# fCPU.net
KiCad netlist of a schematic drawn in EAGLE
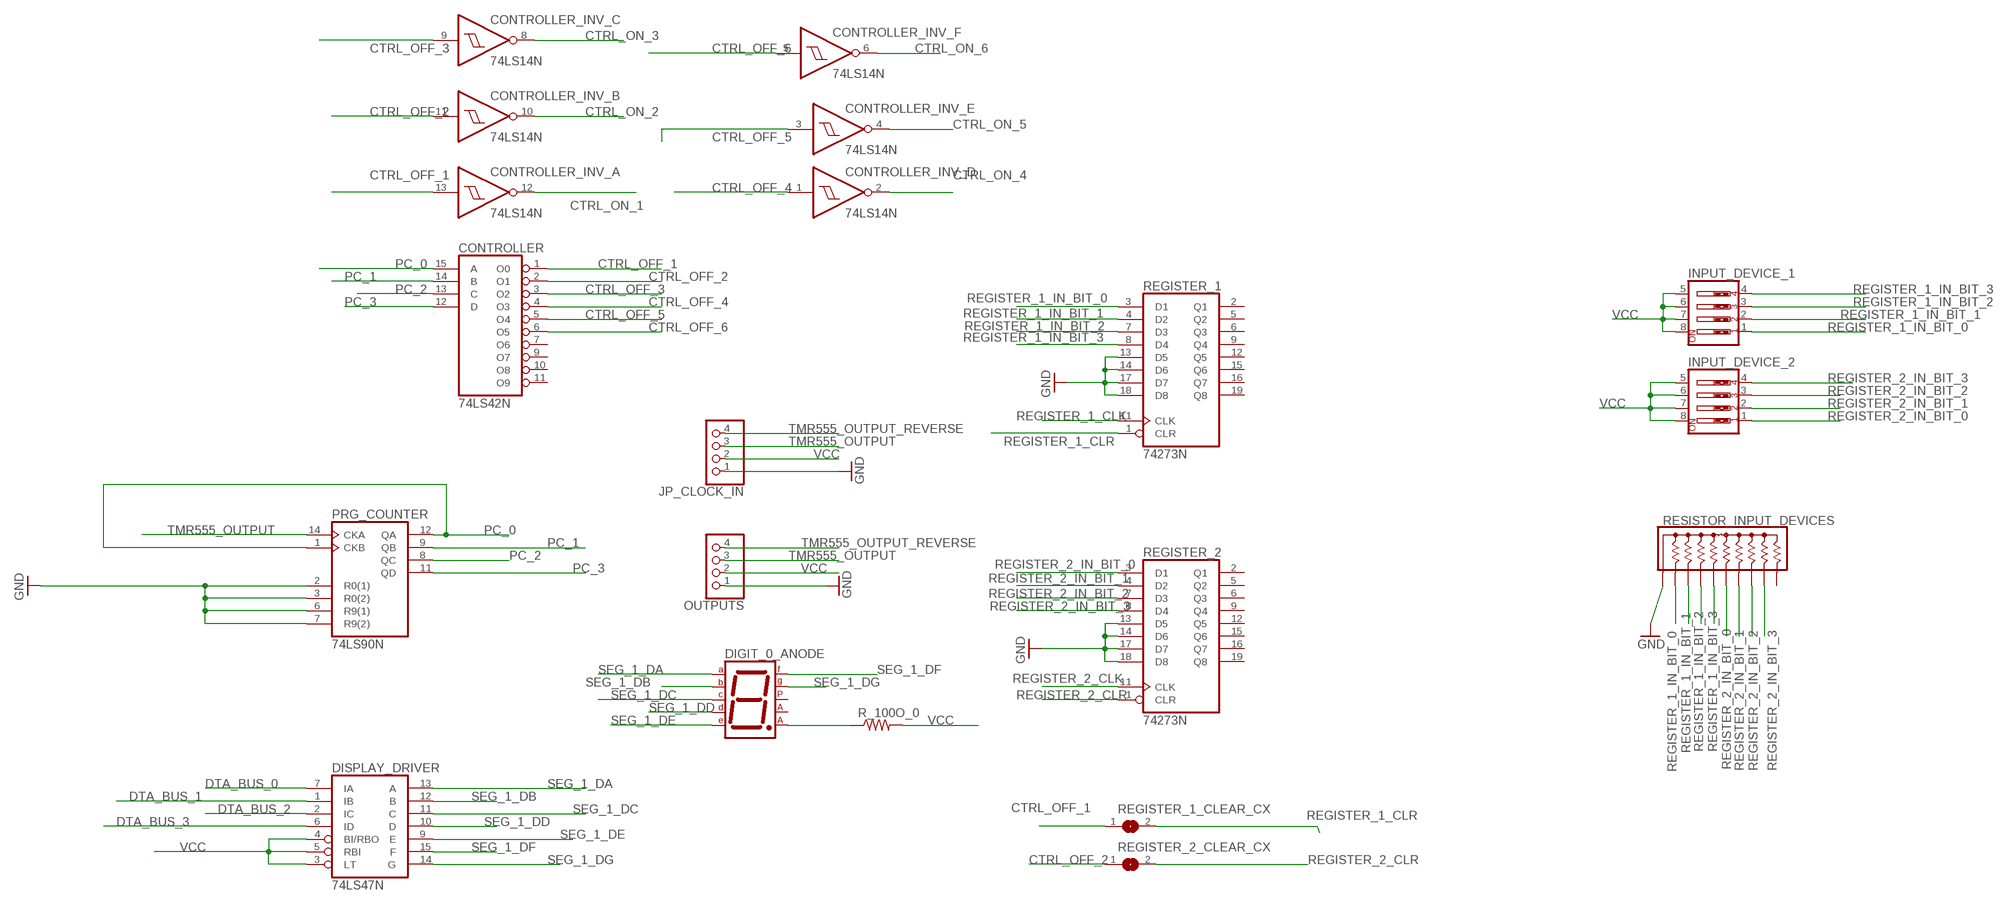
[diagram p0: schematic, sheet 1]

(export (version "E")
  (design (tool "Eeschema 10.0.6"))
  (components
    (comp (ref "CONTROLLER")
      (value "74LS42N")
      (footprint "eagle-import:DIL16")
      (libsource (lib "eagle-import") (part "7442NLS"))
    )
    (comp (ref "CONTROLLER_INV_")
      (value "74LS14N")
      (footprint "eagle-import:DIL14")
      (libsource (lib "eagle-import") (part "7414NLS"))
    )
    (comp (ref "DIGIT_0_ANODE")
      (value "7SEG-CA")
      (footprint "eagle-import:7SEG-13")
      (libsource (lib "eagle-import") (part "7SEG-CA"))
    )
    (comp (ref "DISPLAY_DRIVER")
      (value "74LS47N")
      (footprint "eagle-import:DIL16")
      (libsource (lib "eagle-import") (part "7447NLS"))
    )
    (comp (ref "INPUT_DEVICE_1")
      (value "SW_DIP-4")
      (footprint "eagle-import:EDG-04")
      (libsource (lib "eagle-import") (part "SW_DIP-4"))
    )
    (comp (ref "INPUT_DEVICE_2")
      (value "SW_DIP-4")
      (footprint "eagle-import:EDG-04")
      (libsource (lib "eagle-import") (part "SW_DIP-4"))
    )
    (comp (ref "JP_CLOCK_IN")
      (value "PINHD-1X4")
      (footprint "eagle-import:1X04")
      (libsource (lib "eagle-import") (part "PINHD-1X4"))
    )
    (comp (ref "OUTPUTS")
      (value "PINHD-1X4")
      (footprint "eagle-import:1X04")
      (libsource (lib "eagle-import") (part "PINHD-1X4"))
    )
    (comp (ref "PRG_COUNTER")
      (value "74LS90N")
      (footprint "eagle-import:DIL14")
      (libsource (lib "eagle-import") (part "7490NLS"))
    )
    (comp (ref "REGISTER_1")
      (value "74273N")
      (footprint "eagle-import:DIL20")
      (libsource (lib "eagle-import") (part "74273N"))
    )
    (comp (ref "REGISTER_1_CLEAR_CX")
      (value "SOLDERJUMPERREFLOW")
      (footprint "eagle-import:SOLDERJUMPER_REFLOW")
      (libsource (lib "eagle-import") (part "SOLDERJUMPERREFLOW"))
    )
    (comp (ref "REGISTER_2")
      (value "74273N")
      (footprint "eagle-import:DIL20")
      (libsource (lib "eagle-import") (part "74273N"))
    )
    (comp (ref "REGISTER_2_CLEAR_CX")
      (value "SOLDERJUMPERREFLOW")
      (footprint "eagle-import:SOLDERJUMPER_REFLOW")
      (libsource (lib "eagle-import") (part "SOLDERJUMPERREFLOW"))
    )
    (comp (ref "RESISTOR_INPUT_DEVICES")
      (value "4610X")
      (footprint "eagle-import:SIP10")
      (libsource (lib "eagle-import") (part "4610X"))
    )
    (comp (ref "R_100O_0")
      (value "R-US_R1206")
      (footprint "eagle-import:R1206")
      (libsource (lib "eagle-import") (part "R-US_R1206"))
    )
  )
  (nets
    (net (code "1") (name "/CTRL_OFF_1") (class "Default")
      (node (ref "CONTROLLER") (pin "1") (pinfunction "O0_1") (pintype "output"))
      (node (ref "CONTROLLER_INV_") (pin "13") (pinfunction "I_13") (pintype "input"))
      (node (ref "REGISTER_1_CLEAR_CX") (pin "1") (pinfunction "1_1") (pintype "passive"))
    )
    (net (code "2") (name "/CTRL_OFF_2") (class "Default")
      (node (ref "CONTROLLER") (pin "2") (pinfunction "O1_2") (pintype "output"))
      (node (ref "CONTROLLER_INV_") (pin "11") (pinfunction "I_11") (pintype "input"))
      (node (ref "REGISTER_2_CLEAR_CX") (pin "1") (pinfunction "1_1") (pintype "passive"))
    )
    (net (code "3") (name "/CTRL_OFF_3") (class "Default")
      (node (ref "CONTROLLER") (pin "3") (pinfunction "O2_3") (pintype "output"))
      (node (ref "CONTROLLER_INV_") (pin "9") (pinfunction "I_9") (pintype "input"))
    )
    (net (code "4") (name "/CTRL_OFF_4") (class "Default")
      (node (ref "CONTROLLER") (pin "4") (pinfunction "O3_4") (pintype "output"))
      (node (ref "CONTROLLER_INV_") (pin "1") (pinfunction "I_1") (pintype "input"))
    )
    (net (code "5") (name "/CTRL_OFF_5") (class "Default")
      (node (ref "CONTROLLER") (pin "5") (pinfunction "O4_5") (pintype "output"))
      (node (ref "CONTROLLER_INV_") (pin "3") (pinfunction "I_3") (pintype "input"))
    )
    (net (code "6") (name "/CTRL_OFF_6") (class "Default")
      (node (ref "CONTROLLER") (pin "6") (pinfunction "O5_6") (pintype "output"))
      (node (ref "CONTROLLER_INV_") (pin "5") (pinfunction "I_5") (pintype "input"))
    )
    (net (code "7") (name "/CTRL_ON_1") (class "Default")
      (node (ref "CONTROLLER_INV_") (pin "12") (pinfunction "O_12") (pintype "output"))
    )
    (net (code "8") (name "/CTRL_ON_2") (class "Default")
      (node (ref "CONTROLLER_INV_") (pin "10") (pinfunction "O_10") (pintype "output"))
    )
    (net (code "9") (name "/CTRL_ON_3") (class "Default")
      (node (ref "CONTROLLER_INV_") (pin "8") (pinfunction "O_8") (pintype "output"))
    )
    (net (code "10") (name "/CTRL_ON_4") (class "Default")
      (node (ref "CONTROLLER_INV_") (pin "2") (pinfunction "O_2") (pintype "output"))
    )
    (net (code "11") (name "/CTRL_ON_5") (class "Default")
      (node (ref "CONTROLLER_INV_") (pin "4") (pinfunction "O_4") (pintype "output"))
    )
    (net (code "12") (name "/CTRL_ON_6") (class "Default")
      (node (ref "CONTROLLER_INV_") (pin "6") (pinfunction "O_6") (pintype "output"))
    )
    (net (code "13") (name "/DTA_BUS_0") (class "Default")
      (node (ref "DISPLAY_DRIVER") (pin "7") (pinfunction "IA_7") (pintype "input"))
    )
    (net (code "14") (name "/DTA_BUS_1") (class "Default")
      (node (ref "DISPLAY_DRIVER") (pin "1") (pinfunction "IB_1") (pintype "input"))
    )
    (net (code "15") (name "/DTA_BUS_2") (class "Default")
      (node (ref "DISPLAY_DRIVER") (pin "2") (pinfunction "IC_2") (pintype "input"))
    )
    (net (code "16") (name "/DTA_BUS_3") (class "Default")
      (node (ref "DISPLAY_DRIVER") (pin "6") (pinfunction "ID_6") (pintype "input"))
    )
    (net (code "17") (name "/PC_0") (class "Default")
      (node (ref "CONTROLLER") (pin "15") (pinfunction "A_15") (pintype "input"))
      (node (ref "PRG_COUNTER") (pin "1") (pinfunction "CKB_1") (pintype "input"))
      (node (ref "PRG_COUNTER") (pin "12") (pinfunction "QA_12") (pintype "output"))
    )
    (net (code "18") (name "/PC_1") (class "Default")
      (node (ref "CONTROLLER") (pin "14") (pinfunction "B_14") (pintype "input"))
      (node (ref "PRG_COUNTER") (pin "9") (pinfunction "QB_9") (pintype "output"))
    )
    (net (code "19") (name "/PC_2") (class "Default")
      (node (ref "CONTROLLER") (pin "13") (pinfunction "C_13") (pintype "input"))
      (node (ref "PRG_COUNTER") (pin "8") (pinfunction "QC_8") (pintype "output"))
    )
    (net (code "20") (name "/PC_3") (class "Default")
      (node (ref "CONTROLLER") (pin "12") (pinfunction "D_12") (pintype "input"))
      (node (ref "PRG_COUNTER") (pin "11") (pinfunction "QD_11") (pintype "output"))
    )
    (net (code "21") (name "/REGISTER_1_CLK") (class "Default")
      (node (ref "REGISTER_1") (pin "11") (pinfunction "CLK_11") (pintype "input"))
    )
    (net (code "22") (name "/REGISTER_1_CLR") (class "Default")
      (node (ref "REGISTER_1") (pin "1") (pinfunction "CLR_1") (pintype "input"))
      (node (ref "REGISTER_1_CLEAR_CX") (pin "2") (pinfunction "2_2") (pintype "passive"))
    )
    (net (code "23") (name "/REGISTER_1_IN_BIT_0") (class "Default")
      (node (ref "INPUT_DEVICE_1") (pin "1") (pinfunction "1_1") (pintype "passive"))
      (node (ref "REGISTER_1") (pin "3") (pinfunction "D1_3") (pintype "input"))
      (node (ref "RESISTOR_INPUT_DEVICES") (pin "2") (pinfunction "2_2") (pintype "passive"))
    )
    (net (code "24") (name "/REGISTER_1_IN_BIT_1") (class "Default")
      (node (ref "INPUT_DEVICE_1") (pin "2") (pinfunction "2_2") (pintype "passive"))
      (node (ref "REGISTER_1") (pin "4") (pinfunction "D2_4") (pintype "input"))
      (node (ref "RESISTOR_INPUT_DEVICES") (pin "3") (pinfunction "3_3") (pintype "passive"))
    )
    (net (code "25") (name "/REGISTER_1_IN_BIT_2") (class "Default")
      (node (ref "INPUT_DEVICE_1") (pin "3") (pinfunction "3_3") (pintype "passive"))
      (node (ref "REGISTER_1") (pin "7") (pinfunction "D3_7") (pintype "input"))
      (node (ref "RESISTOR_INPUT_DEVICES") (pin "4") (pinfunction "4_4") (pintype "passive"))
    )
    (net (code "26") (name "/REGISTER_1_IN_BIT_3") (class "Default")
      (node (ref "INPUT_DEVICE_1") (pin "4") (pinfunction "4_4") (pintype "passive"))
      (node (ref "REGISTER_1") (pin "8") (pinfunction "D4_8") (pintype "input"))
      (node (ref "RESISTOR_INPUT_DEVICES") (pin "5") (pinfunction "5_5") (pintype "passive"))
    )
    (net (code "27") (name "/REGISTER_2_CLK") (class "Default")
      (node (ref "REGISTER_2") (pin "11") (pinfunction "CLK_11") (pintype "input"))
    )
    (net (code "28") (name "/REGISTER_2_CLR") (class "Default")
      (node (ref "REGISTER_2") (pin "1") (pinfunction "CLR_1") (pintype "input"))
      (node (ref "REGISTER_2_CLEAR_CX") (pin "2") (pinfunction "2_2") (pintype "passive"))
    )
    (net (code "29") (name "/REGISTER_2_IN_BIT_0") (class "Default")
      (node (ref "INPUT_DEVICE_2") (pin "1") (pinfunction "1_1") (pintype "passive"))
      (node (ref "REGISTER_2") (pin "3") (pinfunction "D1_3") (pintype "input"))
      (node (ref "RESISTOR_INPUT_DEVICES") (pin "6") (pinfunction "6_6") (pintype "passive"))
    )
    (net (code "30") (name "/REGISTER_2_IN_BIT_1") (class "Default")
      (node (ref "INPUT_DEVICE_2") (pin "2") (pinfunction "2_2") (pintype "passive"))
      (node (ref "REGISTER_2") (pin "4") (pinfunction "D2_4") (pintype "input"))
      (node (ref "RESISTOR_INPUT_DEVICES") (pin "7") (pinfunction "7_7") (pintype "passive"))
    )
    (net (code "31") (name "/REGISTER_2_IN_BIT_2") (class "Default")
      (node (ref "INPUT_DEVICE_2") (pin "3") (pinfunction "3_3") (pintype "passive"))
      (node (ref "REGISTER_2") (pin "7") (pinfunction "D3_7") (pintype "input"))
      (node (ref "RESISTOR_INPUT_DEVICES") (pin "8") (pinfunction "8_8") (pintype "passive"))
    )
    (net (code "32") (name "/REGISTER_2_IN_BIT_3") (class "Default")
      (node (ref "INPUT_DEVICE_2") (pin "4") (pinfunction "4_4") (pintype "passive"))
      (node (ref "REGISTER_2") (pin "8") (pinfunction "D4_8") (pintype "input"))
      (node (ref "RESISTOR_INPUT_DEVICES") (pin "9") (pinfunction "9_9") (pintype "passive"))
    )
    (net (code "33") (name "/SEG_1_DA") (class "Default")
      (node (ref "DIGIT_0_ANODE") (pin "7") (pinfunction "A_7") (pintype "passive"))
      (node (ref "DISPLAY_DRIVER") (pin "13") (pinfunction "A_13") (pintype "output"))
    )
    (net (code "34") (name "/SEG_1_DB") (class "Default")
      (node (ref "DIGIT_0_ANODE") (pin "6") (pinfunction "B_6") (pintype "passive"))
      (node (ref "DISPLAY_DRIVER") (pin "12") (pinfunction "B_12") (pintype "output"))
    )
    (net (code "35") (name "/SEG_1_DC") (class "Default")
      (node (ref "DIGIT_0_ANODE") (pin "4") (pinfunction "C_4") (pintype "passive"))
      (node (ref "DISPLAY_DRIVER") (pin "11") (pinfunction "C_11") (pintype "output"))
    )
    (net (code "36") (name "/SEG_1_DD") (class "Default")
      (node (ref "DIGIT_0_ANODE") (pin "2") (pinfunction "D_2") (pintype "passive"))
      (node (ref "DISPLAY_DRIVER") (pin "10") (pinfunction "D_10") (pintype "output"))
    )
    (net (code "37") (name "/SEG_1_DE") (class "Default")
      (node (ref "DIGIT_0_ANODE") (pin "1") (pinfunction "E_1") (pintype "passive"))
      (node (ref "DISPLAY_DRIVER") (pin "9") (pinfunction "E_9") (pintype "output"))
    )
    (net (code "38") (name "/SEG_1_DF") (class "Default")
      (node (ref "DIGIT_0_ANODE") (pin "9") (pinfunction "F_9") (pintype "passive"))
      (node (ref "DISPLAY_DRIVER") (pin "15") (pinfunction "F_15") (pintype "output"))
    )
    (net (code "39") (name "/SEG_1_DG") (class "Default")
      (node (ref "DIGIT_0_ANODE") (pin "10") (pinfunction "G_10") (pintype "passive"))
      (node (ref "DISPLAY_DRIVER") (pin "14") (pinfunction "G_14") (pintype "output"))
    )
    (net (code "40") (name "/TMR555_OUTPUT") (class "Default")
      (node (ref "JP_CLOCK_IN") (pin "3") (pinfunction "3_3") (pintype "passive"))
      (node (ref "OUTPUTS") (pin "3") (pinfunction "3_3") (pintype "passive"))
      (node (ref "PRG_COUNTER") (pin "14") (pinfunction "CKA_14") (pintype "input"))
    )
    (net (code "41") (name "/TMR555_OUTPUT_REVERSE") (class "Default")
      (node (ref "JP_CLOCK_IN") (pin "4") (pinfunction "4_4") (pintype "passive"))
      (node (ref "OUTPUTS") (pin "4") (pinfunction "4_4") (pintype "passive"))
    )
    (net (code "42") (name "/VCC") (class "Default")
      (node (ref "DISPLAY_DRIVER") (pin "3") (pinfunction "LT_3") (pintype "input"))
      (node (ref "DISPLAY_DRIVER") (pin "4") (pinfunction "BI/RBO_4") (pintype "input"))
      (node (ref "DISPLAY_DRIVER") (pin "5") (pinfunction "RBI_5") (pintype "input"))
      (node (ref "INPUT_DEVICE_1") (pin "5") (pinfunction "5_5") (pintype "passive"))
      (node (ref "INPUT_DEVICE_1") (pin "6") (pinfunction "6_6") (pintype "passive"))
      (node (ref "INPUT_DEVICE_1") (pin "7") (pinfunction "7_7") (pintype "passive"))
      (node (ref "INPUT_DEVICE_1") (pin "8") (pinfunction "8_8") (pintype "passive"))
      (node (ref "INPUT_DEVICE_2") (pin "5") (pinfunction "5_5") (pintype "passive"))
      (node (ref "INPUT_DEVICE_2") (pin "6") (pinfunction "6_6") (pintype "passive"))
      (node (ref "INPUT_DEVICE_2") (pin "7") (pinfunction "7_7") (pintype "passive"))
      (node (ref "INPUT_DEVICE_2") (pin "8") (pinfunction "8_8") (pintype "passive"))
      (node (ref "JP_CLOCK_IN") (pin "2") (pinfunction "2_2") (pintype "passive"))
      (node (ref "OUTPUTS") (pin "2") (pinfunction "2_2") (pintype "passive"))
      (node (ref "R_100O_0") (pin "2") (pinfunction "2_2") (pintype "passive"))
    )
    (net (code "43") (name "GND") (class "Default")
      (node (ref "JP_CLOCK_IN") (pin "1") (pinfunction "1_1") (pintype "passive"))
      (node (ref "OUTPUTS") (pin "1") (pinfunction "1_1") (pintype "passive"))
      (node (ref "PRG_COUNTER") (pin "2") (pinfunction "R0(1)_2") (pintype "input"))
      (node (ref "PRG_COUNTER") (pin "3") (pinfunction "R0(2)_3") (pintype "input"))
      (node (ref "PRG_COUNTER") (pin "6") (pinfunction "R9(1)_6") (pintype "input"))
      (node (ref "PRG_COUNTER") (pin "7") (pinfunction "R9(2)_7") (pintype "input"))
      (node (ref "REGISTER_1") (pin "13") (pinfunction "D5_13") (pintype "input"))
      (node (ref "REGISTER_1") (pin "14") (pinfunction "D6_14") (pintype "input"))
      (node (ref "REGISTER_1") (pin "17") (pinfunction "D7_17") (pintype "input"))
      (node (ref "REGISTER_1") (pin "18") (pinfunction "D8_18") (pintype "input"))
      (node (ref "REGISTER_2") (pin "13") (pinfunction "D5_13") (pintype "input"))
      (node (ref "REGISTER_2") (pin "14") (pinfunction "D6_14") (pintype "input"))
      (node (ref "REGISTER_2") (pin "17") (pinfunction "D7_17") (pintype "input"))
      (node (ref "REGISTER_2") (pin "18") (pinfunction "D8_18") (pintype "input"))
      (node (ref "RESISTOR_INPUT_DEVICES") (pin "1") (pinfunction "1_1") (pintype "passive"))
    )
    (net (code "44") (name "Net-(DIGIT_0_ANODE-CA2)") (class "Default")
      (node (ref "DIGIT_0_ANODE") (pin "8") (pinfunction "CA2_8") (pintype "passive"))
      (node (ref "R_100O_0") (pin "1") (pinfunction "1_1") (pintype "passive"))
    )
    (net (code "45") (name "unconnected-(CONTROLLERA-O6-Pad7)") (class "Default")
      (node (ref "CONTROLLER") (pin "7") (pinfunction "O6_7") (pintype "output"))
    )
    (net (code "46") (name "unconnected-(CONTROLLERA-O7-Pad9)") (class "Default")
      (node (ref "CONTROLLER") (pin "9") (pinfunction "O7_9") (pintype "output"))
    )
    (net (code "47") (name "unconnected-(CONTROLLERA-O8-Pad10)") (class "Default")
      (node (ref "CONTROLLER") (pin "10") (pinfunction "O8_10") (pintype "output"))
    )
    (net (code "48") (name "unconnected-(CONTROLLERA-O9-Pad11)") (class "Default")
      (node (ref "CONTROLLER") (pin "11") (pinfunction "O9_11") (pintype "output"))
    )
    (net (code "49") (name "unconnected-(DIGIT_0_ANODE-CA1-Pad3)") (class "Default")
      (node (ref "DIGIT_0_ANODE") (pin "3") (pinfunction "CA1_3") (pintype "passive"))
    )
    (net (code "50") (name "unconnected-(DIGIT_0_ANODE-DP-Pad5)") (class "Default")
      (node (ref "DIGIT_0_ANODE") (pin "5") (pinfunction "DP_5") (pintype "passive"))
    )
    (net (code "51") (name "unconnected-(REGISTER_1A-Q1-Pad2)") (class "Default")
      (node (ref "REGISTER_1") (pin "2") (pinfunction "Q1_2") (pintype "output"))
    )
    (net (code "52") (name "unconnected-(REGISTER_1A-Q2-Pad5)") (class "Default")
      (node (ref "REGISTER_1") (pin "5") (pinfunction "Q2_5") (pintype "output"))
    )
    (net (code "53") (name "unconnected-(REGISTER_1A-Q3-Pad6)") (class "Default")
      (node (ref "REGISTER_1") (pin "6") (pinfunction "Q3_6") (pintype "output"))
    )
    (net (code "54") (name "unconnected-(REGISTER_1A-Q4-Pad9)") (class "Default")
      (node (ref "REGISTER_1") (pin "9") (pinfunction "Q4_9") (pintype "output"))
    )
    (net (code "55") (name "unconnected-(REGISTER_1A-Q5-Pad12)") (class "Default")
      (node (ref "REGISTER_1") (pin "12") (pinfunction "Q5_12") (pintype "output"))
    )
    (net (code "56") (name "unconnected-(REGISTER_1A-Q6-Pad15)") (class "Default")
      (node (ref "REGISTER_1") (pin "15") (pinfunction "Q6_15") (pintype "output"))
    )
    (net (code "57") (name "unconnected-(REGISTER_1A-Q7-Pad16)") (class "Default")
      (node (ref "REGISTER_1") (pin "16") (pinfunction "Q7_16") (pintype "output"))
    )
    (net (code "58") (name "unconnected-(REGISTER_1A-Q8-Pad19)") (class "Default")
      (node (ref "REGISTER_1") (pin "19") (pinfunction "Q8_19") (pintype "output"))
    )
    (net (code "59") (name "unconnected-(REGISTER_2A-Q1-Pad2)") (class "Default")
      (node (ref "REGISTER_2") (pin "2") (pinfunction "Q1_2") (pintype "output"))
    )
    (net (code "60") (name "unconnected-(REGISTER_2A-Q2-Pad5)") (class "Default")
      (node (ref "REGISTER_2") (pin "5") (pinfunction "Q2_5") (pintype "output"))
    )
    (net (code "61") (name "unconnected-(REGISTER_2A-Q3-Pad6)") (class "Default")
      (node (ref "REGISTER_2") (pin "6") (pinfunction "Q3_6") (pintype "output"))
    )
    (net (code "62") (name "unconnected-(REGISTER_2A-Q4-Pad9)") (class "Default")
      (node (ref "REGISTER_2") (pin "9") (pinfunction "Q4_9") (pintype "output"))
    )
    (net (code "63") (name "unconnected-(REGISTER_2A-Q5-Pad12)") (class "Default")
      (node (ref "REGISTER_2") (pin "12") (pinfunction "Q5_12") (pintype "output"))
    )
    (net (code "64") (name "unconnected-(REGISTER_2A-Q6-Pad15)") (class "Default")
      (node (ref "REGISTER_2") (pin "15") (pinfunction "Q6_15") (pintype "output"))
    )
    (net (code "65") (name "unconnected-(REGISTER_2A-Q7-Pad16)") (class "Default")
      (node (ref "REGISTER_2") (pin "16") (pinfunction "Q7_16") (pintype "output"))
    )
    (net (code "66") (name "unconnected-(REGISTER_2A-Q8-Pad19)") (class "Default")
      (node (ref "REGISTER_2") (pin "19") (pinfunction "Q8_19") (pintype "output"))
    )
    (net (code "67") (name "unconnected-(RESISTOR_INPUT_DEVICES-Pad10)") (class "Default")
      (node (ref "RESISTOR_INPUT_DEVICES") (pin "10") (pinfunction "10_10") (pintype "passive"))
    )
  )
)
